# kartusho2.net
KiCad netlist of a schematic drawn in EAGLE
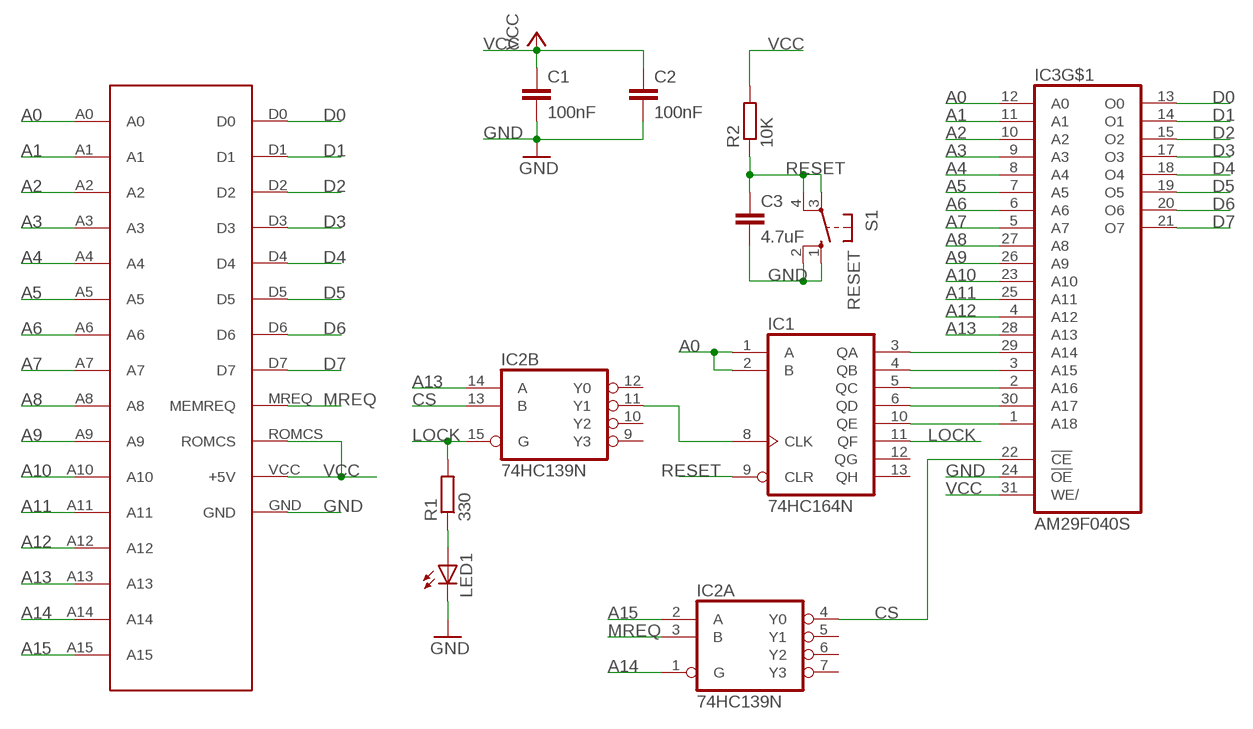
[diagram p0: schematic, sheet 1]

(export (version "E")
  (design (tool "Eeschema 10.0.6"))
  (components
    (comp (ref "C1")
      (value "100nF")
      (footprint "eagle-import:C025-025X050")
      (libsource (lib "eagle-import") (part "C-EU025-025X050"))
    )
    (comp (ref "C2")
      (value "100nF")
      (footprint "eagle-import:C025-025X050")
      (libsource (lib "eagle-import") (part "C-EU025-025X050"))
    )
    (comp (ref "C3")
      (value "4.7uF")
      (footprint "eagle-import:C025-025X050")
      (libsource (lib "eagle-import") (part "C-EU025-025X050"))
    )
    (comp (ref "IC1")
      (value "74HC164N")
      (footprint "eagle-import:DIL14")
      (libsource (lib "eagle-import") (part "74164NHC"))
    )
    (comp (ref "IC2")
      (value "74HC139N")
      (footprint "eagle-import:DIL16")
      (libsource (lib "eagle-import") (part "74139NHC"))
    )
    (comp (ref "IC3")
      (value "AM29F040S")
      (footprint "eagle-import:PLCC-SR32")
      (libsource (lib "eagle-import") (part "AM29F040S"))
    )
    (comp (ref "LED1")
      (value "LED3MM")
      (footprint "eagle-import:LED3MM")
      (libsource (lib "eagle-import") (part "LED3MM"))
    )
    (comp (ref "R1")
      (value "330")
      (footprint "eagle-import:0204_7")
      (libsource (lib "eagle-import") (part "R-EU_0204/7"))
    )
    (comp (ref "R2")
      (value "10K")
      (footprint "eagle-import:0204_7")
      (libsource (lib "eagle-import") (part "R-EU_0204/7"))
    )
    (comp (ref "S1")
      (value "RESET")
      (footprint "eagle-import:B3F-10XX")
      (fields (field (name "MPN") "B3F-1000"))
      (libsource (lib "eagle-import") (part "10-XX"))
    )
    (comp (ref "U$1")
      (value "IF2BUS")
      (footprint "eagle-import:BUS_CARTUCHO_IF2")
      (libsource (lib "eagle-import") (part "IF2BUS"))
    )
  )
  (nets
    (net (code "1") (name "/A0") (class "Default")
      (node (ref "IC1") (pin "1") (pinfunction "A_1") (pintype "input"))
      (node (ref "IC1") (pin "2") (pinfunction "B_2") (pintype "input"))
      (node (ref "IC3") (pin "12") (pinfunction "A0_12") (pintype "input"))
      (node (ref "U$1") (pin "A0") (pinfunction "A0_A0") (pintype "bidirectional"))
    )
    (net (code "2") (name "/A1") (class "Default")
      (node (ref "IC3") (pin "11") (pinfunction "A1_11") (pintype "input"))
      (node (ref "U$1") (pin "A1") (pinfunction "A1_A1") (pintype "bidirectional"))
    )
    (net (code "3") (name "/A2") (class "Default")
      (node (ref "IC3") (pin "10") (pinfunction "A2_10") (pintype "input"))
      (node (ref "U$1") (pin "A2") (pinfunction "A2_A2") (pintype "bidirectional"))
    )
    (net (code "4") (name "/A3") (class "Default")
      (node (ref "IC3") (pin "9") (pinfunction "A3_9") (pintype "input"))
      (node (ref "U$1") (pin "A3") (pinfunction "A3_A3") (pintype "bidirectional"))
    )
    (net (code "5") (name "/A4") (class "Default")
      (node (ref "IC3") (pin "8") (pinfunction "A4_8") (pintype "input"))
      (node (ref "U$1") (pin "A4") (pinfunction "A4_A4") (pintype "bidirectional"))
    )
    (net (code "6") (name "/A5") (class "Default")
      (node (ref "IC3") (pin "7") (pinfunction "A5_7") (pintype "input"))
      (node (ref "U$1") (pin "A5") (pinfunction "A5_A5") (pintype "bidirectional"))
    )
    (net (code "7") (name "/A6") (class "Default")
      (node (ref "IC3") (pin "6") (pinfunction "A6_6") (pintype "input"))
      (node (ref "U$1") (pin "A6") (pinfunction "A6_A6") (pintype "bidirectional"))
    )
    (net (code "8") (name "/A7") (class "Default")
      (node (ref "IC3") (pin "5") (pinfunction "A7_5") (pintype "input"))
      (node (ref "U$1") (pin "A7") (pinfunction "A7_A7") (pintype "bidirectional"))
    )
    (net (code "9") (name "/A8") (class "Default")
      (node (ref "IC3") (pin "27") (pinfunction "A8_27") (pintype "input"))
      (node (ref "U$1") (pin "A8") (pinfunction "A8_A8") (pintype "bidirectional"))
    )
    (net (code "10") (name "/A9") (class "Default")
      (node (ref "IC3") (pin "26") (pinfunction "A9_26") (pintype "input"))
      (node (ref "U$1") (pin "A9") (pinfunction "A9_A9") (pintype "bidirectional"))
    )
    (net (code "11") (name "/A10") (class "Default")
      (node (ref "IC3") (pin "23") (pinfunction "A10_23") (pintype "input"))
      (node (ref "U$1") (pin "A10") (pinfunction "A10_A10") (pintype "bidirectional"))
    )
    (net (code "12") (name "/A11") (class "Default")
      (node (ref "IC3") (pin "25") (pinfunction "A11_25") (pintype "input"))
      (node (ref "U$1") (pin "A11") (pinfunction "A11_A11") (pintype "bidirectional"))
    )
    (net (code "13") (name "/A12") (class "Default")
      (node (ref "IC3") (pin "4") (pinfunction "A12_4") (pintype "input"))
      (node (ref "U$1") (pin "A12") (pinfunction "A12_A12") (pintype "bidirectional"))
    )
    (net (code "14") (name "/A13") (class "Default")
      (node (ref "IC2") (pin "14") (pinfunction "A_14") (pintype "input"))
      (node (ref "IC3") (pin "28") (pinfunction "A13_28") (pintype "input"))
      (node (ref "U$1") (pin "A13") (pinfunction "A13_A13") (pintype "bidirectional"))
    )
    (net (code "15") (name "/A14") (class "Default")
      (node (ref "IC2") (pin "1") (pinfunction "G_1") (pintype "input"))
      (node (ref "U$1") (pin "A14") (pinfunction "A14_A14") (pintype "bidirectional"))
    )
    (net (code "16") (name "/A15") (class "Default")
      (node (ref "IC2") (pin "2") (pinfunction "A_2") (pintype "input"))
      (node (ref "U$1") (pin "A15") (pinfunction "A15_A15") (pintype "bidirectional"))
    )
    (net (code "17") (name "/CS") (class "Default")
      (node (ref "IC2") (pin "13") (pinfunction "B_13") (pintype "input"))
      (node (ref "IC2") (pin "4") (pinfunction "Y0_4") (pintype "output"))
      (node (ref "IC3") (pin "22") (pinfunction "~{CE}_22") (pintype "input"))
    )
    (net (code "18") (name "/D0") (class "Default")
      (node (ref "IC3") (pin "13") (pinfunction "O0_13") (pintype "tri_state"))
      (node (ref "U$1") (pin "D0") (pinfunction "D0_D0") (pintype "bidirectional"))
    )
    (net (code "19") (name "/D1") (class "Default")
      (node (ref "IC3") (pin "14") (pinfunction "O1_14") (pintype "tri_state"))
      (node (ref "U$1") (pin "D1") (pinfunction "D1_D1") (pintype "bidirectional"))
    )
    (net (code "20") (name "/D2") (class "Default")
      (node (ref "IC3") (pin "15") (pinfunction "O2_15") (pintype "tri_state"))
      (node (ref "U$1") (pin "D2") (pinfunction "D2_D2") (pintype "bidirectional"))
    )
    (net (code "21") (name "/D3") (class "Default")
      (node (ref "IC3") (pin "17") (pinfunction "O3_17") (pintype "tri_state"))
      (node (ref "U$1") (pin "D3") (pinfunction "D3_D3") (pintype "bidirectional"))
    )
    (net (code "22") (name "/D4") (class "Default")
      (node (ref "IC3") (pin "18") (pinfunction "O4_18") (pintype "tri_state"))
      (node (ref "U$1") (pin "D4") (pinfunction "D4_D4") (pintype "bidirectional"))
    )
    (net (code "23") (name "/D5") (class "Default")
      (node (ref "IC3") (pin "19") (pinfunction "O5_19") (pintype "tri_state"))
      (node (ref "U$1") (pin "D5") (pinfunction "D5_D5") (pintype "bidirectional"))
    )
    (net (code "24") (name "/D6") (class "Default")
      (node (ref "IC3") (pin "20") (pinfunction "O6_20") (pintype "tri_state"))
      (node (ref "U$1") (pin "D6") (pinfunction "D6_D6") (pintype "bidirectional"))
    )
    (net (code "25") (name "/D7") (class "Default")
      (node (ref "IC3") (pin "21") (pinfunction "O7_21") (pintype "tri_state"))
      (node (ref "U$1") (pin "D7") (pinfunction "D7_D7") (pintype "bidirectional"))
    )
    (net (code "26") (name "/LOCK") (class "Default")
      (node (ref "IC1") (pin "11") (pinfunction "QF_11") (pintype "output"))
      (node (ref "IC2") (pin "15") (pinfunction "G_15") (pintype "input"))
      (node (ref "R1") (pin "2") (pinfunction "2_2") (pintype "passive"))
    )
    (net (code "27") (name "/MREQ") (class "Default")
      (node (ref "IC2") (pin "3") (pinfunction "B_3") (pintype "input"))
      (node (ref "U$1") (pin "MREQ") (pinfunction "MEMREQ_MREQ") (pintype "bidirectional"))
    )
    (net (code "28") (name "/RESET") (class "Default")
      (node (ref "C3") (pin "1") (pinfunction "1_1") (pintype "passive"))
      (node (ref "IC1") (pin "9") (pinfunction "CLR_9") (pintype "input"))
      (node (ref "R2") (pin "1") (pinfunction "1_1") (pintype "passive"))
      (node (ref "S1") (pin "3") (pinfunction "P_3") (pintype "passive"))
      (node (ref "S1") (pin "4") (pinfunction "P1_4") (pintype "passive"))
    )
    (net (code "29") (name "GND") (class "Default")
      (node (ref "C1") (pin "2") (pinfunction "2_2") (pintype "passive"))
      (node (ref "C2") (pin "2") (pinfunction "2_2") (pintype "passive"))
      (node (ref "C3") (pin "2") (pinfunction "2_2") (pintype "passive"))
      (node (ref "IC3") (pin "24") (pinfunction "~{OE}_24") (pintype "input"))
      (node (ref "LED1") (pin "K") (pinfunction "C_K") (pintype "passive"))
      (node (ref "S1") (pin "1") (pinfunction "S_1") (pintype "passive"))
      (node (ref "S1") (pin "2") (pinfunction "S1_2") (pintype "passive"))
      (node (ref "U$1") (pin "GND") (pinfunction "GND_GND") (pintype "bidirectional"))
    )
    (net (code "30") (name "Net-(IC1A-CLK)") (class "Default")
      (node (ref "IC1") (pin "8") (pinfunction "CLK_8") (pintype "input"))
      (node (ref "IC2") (pin "11") (pinfunction "Y1_11") (pintype "output"))
    )
    (net (code "31") (name "Net-(IC1A-QA)") (class "Default")
      (node (ref "IC1") (pin "3") (pinfunction "QA_3") (pintype "output"))
      (node (ref "IC3") (pin "29") (pinfunction "A14_29") (pintype "input"))
    )
    (net (code "32") (name "Net-(IC1A-QB)") (class "Default")
      (node (ref "IC1") (pin "4") (pinfunction "QB_4") (pintype "output"))
      (node (ref "IC3") (pin "3") (pinfunction "A15_3") (pintype "input"))
    )
    (net (code "33") (name "Net-(IC1A-QC)") (class "Default")
      (node (ref "IC1") (pin "5") (pinfunction "QC_5") (pintype "output"))
      (node (ref "IC3") (pin "2") (pinfunction "A16_2") (pintype "input"))
    )
    (net (code "34") (name "Net-(IC1A-QD)") (class "Default")
      (node (ref "IC1") (pin "6") (pinfunction "QD_6") (pintype "output"))
      (node (ref "IC3") (pin "30") (pinfunction "A17_30") (pintype "input"))
    )
    (net (code "35") (name "Net-(IC1A-QE)") (class "Default")
      (node (ref "IC1") (pin "10") (pinfunction "QE_10") (pintype "output"))
      (node (ref "IC3") (pin "1") (pinfunction "A18_1") (pintype "input"))
    )
    (net (code "36") (name "Net-(LED1-PadA)") (class "Default")
      (node (ref "LED1") (pin "A") (pinfunction "A_A") (pintype "passive"))
      (node (ref "R1") (pin "1") (pinfunction "1_1") (pintype "passive"))
    )
    (net (code "37") (name "VCC") (class "Default")
      (node (ref "C1") (pin "1") (pinfunction "1_1") (pintype "passive"))
      (node (ref "C2") (pin "1") (pinfunction "1_1") (pintype "passive"))
      (node (ref "IC3") (pin "31") (pinfunction "WE/_31") (pintype "input"))
      (node (ref "R2") (pin "2") (pinfunction "2_2") (pintype "passive"))
      (node (ref "U$1") (pin "ROMCS") (pinfunction "ROMCS_ROMCS") (pintype "bidirectional"))
      (node (ref "U$1") (pin "VCC") (pinfunction "+5V_VCC") (pintype "bidirectional"))
    )
    (net (code "38") (name "unconnected-(IC1A-QG-Pad12)") (class "Default")
      (node (ref "IC1") (pin "12") (pinfunction "QG_12") (pintype "output"))
    )
    (net (code "39") (name "unconnected-(IC1A-QH-Pad13)") (class "Default")
      (node (ref "IC1") (pin "13") (pinfunction "QH_13") (pintype "output"))
    )
    (net (code "40") (name "unconnected-(IC2A-Y1-Pad5)") (class "Default")
      (node (ref "IC2") (pin "5") (pinfunction "Y1_5") (pintype "output"))
    )
    (net (code "41") (name "unconnected-(IC2A-Y2-Pad6)") (class "Default")
      (node (ref "IC2") (pin "6") (pinfunction "Y2_6") (pintype "output"))
    )
    (net (code "42") (name "unconnected-(IC2A-Y3-Pad7)") (class "Default")
      (node (ref "IC2") (pin "7") (pinfunction "Y3_7") (pintype "output"))
    )
    (net (code "43") (name "unconnected-(IC2B-Y0-Pad12)") (class "Default")
      (node (ref "IC2") (pin "12") (pinfunction "Y0_12") (pintype "output"))
    )
    (net (code "44") (name "unconnected-(IC2B-Y2-Pad10)") (class "Default")
      (node (ref "IC2") (pin "10") (pinfunction "Y2_10") (pintype "output"))
    )
    (net (code "45") (name "unconnected-(IC2B-Y3-Pad9)") (class "Default")
      (node (ref "IC2") (pin "9") (pinfunction "Y3_9") (pintype "output"))
    )
  )
)
